# Variable_Voltage.net
KiCad netlist of a schematic drawn in EAGLE
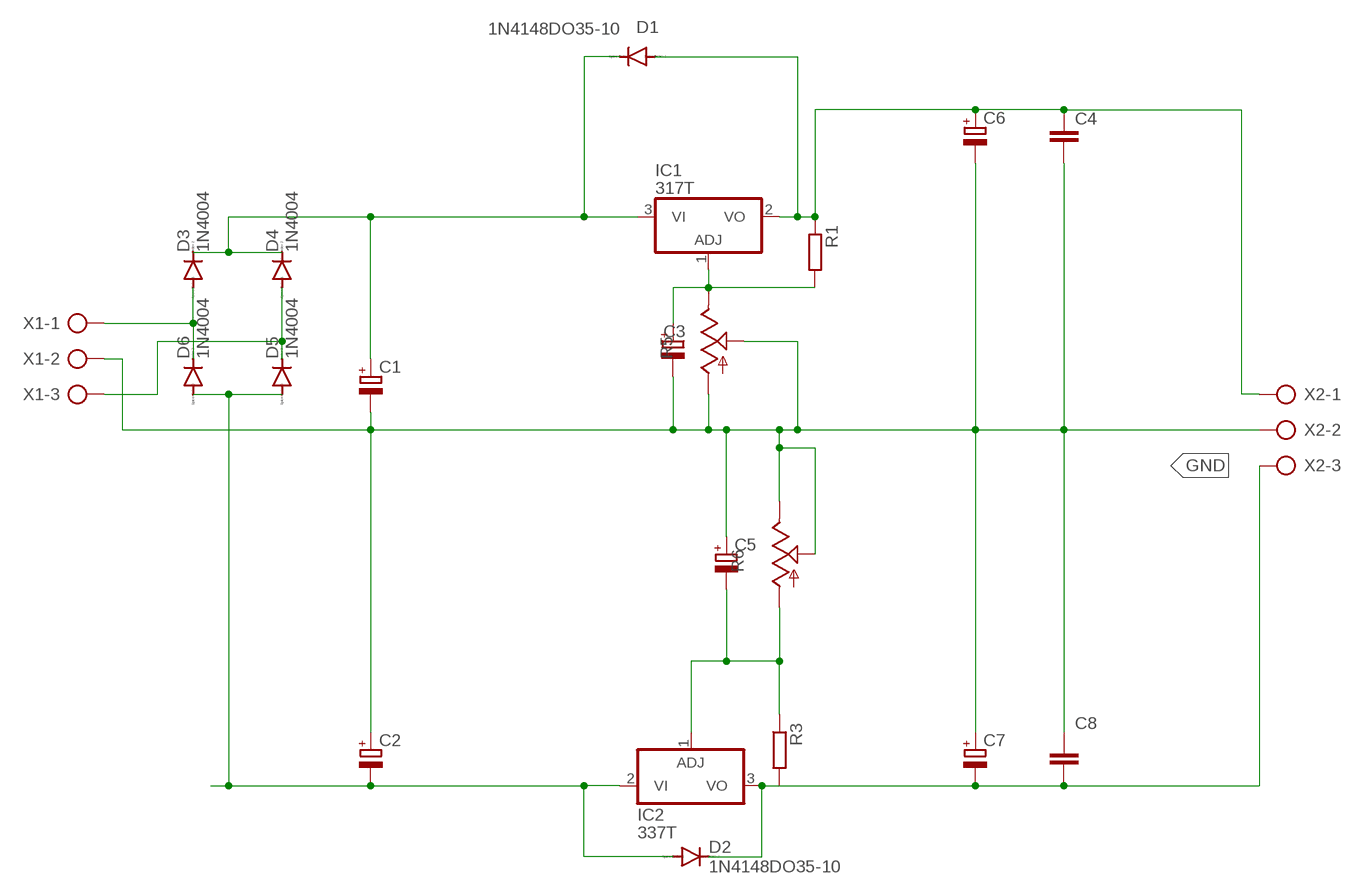
[diagram p0: schematic, sheet 1]

(export (version "E")
  (design (tool "Eeschema 10.0.6"))
  (components
    (comp (ref "C1")
      (value "CPOL-EUE5-8.5")
      (footprint "eagle-import:E5-8,5")
      (libsource (lib "eagle-import") (part "CPOL-EUE5-8.5"))
    )
    (comp (ref "C2")
      (value "CPOL-EUE5-8.5")
      (footprint "eagle-import:E5-8,5")
      (libsource (lib "eagle-import") (part "CPOL-EUE5-8.5"))
    )
    (comp (ref "C3")
      (value "CPOL-EUE2-4")
      (footprint "eagle-import:E2-4")
      (libsource (lib "eagle-import") (part "CPOL-EUE2-4"))
    )
    (comp (ref "C4")
      (value "C2,5-3")
      (footprint "eagle-import:C2.5-3")
      (libsource (lib "eagle-import") (part "C2,5-3"))
    )
    (comp (ref "C5")
      (value "CPOL-EUE2-4")
      (footprint "eagle-import:E2-4")
      (libsource (lib "eagle-import") (part "CPOL-EUE2-4"))
    )
    (comp (ref "C6")
      (value "CPOL-EUE2.5-4V")
      (footprint "eagle-import:E2,5RE")
      (libsource (lib "eagle-import") (part "CPOL-EUE2.5-4V"))
    )
    (comp (ref "C7")
      (value "CPOL-EUE2.5-4V")
      (footprint "eagle-import:E2,5RE")
      (libsource (lib "eagle-import") (part "CPOL-EUE2.5-4V"))
    )
    (comp (ref "C8")
      (value "C2,5-3")
      (footprint "eagle-import:C2.5-3")
      (libsource (lib "eagle-import") (part "C2,5-3"))
    )
    (comp (ref "D1")
      (value "1N4148DO35-10")
      (footprint "eagle-import:DO35-10")
      (libsource (lib "eagle-import") (part "1N4148DO35-10"))
    )
    (comp (ref "D2")
      (value "1N4148DO35-10")
      (footprint "eagle-import:DO35-10")
      (libsource (lib "eagle-import") (part "1N4148DO35-10"))
    )
    (comp (ref "D3")
      (value "1N4004")
      (footprint "eagle-import:DO41-10")
      (libsource (lib "eagle-import") (part "1N4004"))
    )
    (comp (ref "D4")
      (value "1N4004")
      (footprint "eagle-import:DO41-10")
      (libsource (lib "eagle-import") (part "1N4004"))
    )
    (comp (ref "D5")
      (value "1N4004")
      (footprint "eagle-import:DO41-10")
      (libsource (lib "eagle-import") (part "1N4004"))
    )
    (comp (ref "D6")
      (value "1N4004")
      (footprint "eagle-import:DO41-10")
      (libsource (lib "eagle-import") (part "1N4004"))
    )
    (comp (ref "IC1")
      (value "317T")
      (footprint "eagle-import:TO220H")
      (libsource (lib "eagle-import") (part "317T"))
    )
    (comp (ref "IC2")
      (value "337T")
      (footprint "eagle-import:TO220H")
      (libsource (lib "eagle-import") (part "337T"))
    )
    (comp (ref "R1")
      (value "R-EU_0204/7")
      (footprint "eagle-import:0204_7")
      (libsource (lib "eagle-import") (part "R-EU_0204/7"))
    )
    (comp (ref "R3")
      (value "R-EU_0204/7")
      (footprint "eagle-import:0204_7")
      (libsource (lib "eagle-import") (part "R-EU_0204/7"))
    )
    (comp (ref "R5")
      (value "TRIM_US-B25V")
      (footprint "eagle-import:B25V")
      (libsource (lib "eagle-import") (part "TRIM_US-B25V"))
    )
    (comp (ref "R6")
      (value "TRIM_US-B25V")
      (footprint "eagle-import:B25V")
      (libsource (lib "eagle-import") (part "TRIM_US-B25V"))
    )
    (comp (ref "X1")
      (value "AK300/3")
      (footprint "eagle-import:AK300_3")
      (libsource (lib "eagle-import") (part "AK300/3"))
    )
    (comp (ref "X2")
      (value "AK300/3")
      (footprint "eagle-import:AK300_3")
      (libsource (lib "eagle-import") (part "AK300/3"))
    )
  )
  (nets
    (net (code "1") (name "GND") (class "Default")
      (node (ref "C1") (pin "-") (pinfunction "-_-") (pintype "passive"))
      (node (ref "C2") (pin "+") (pinfunction "+_+") (pintype "passive"))
      (node (ref "C3") (pin "-") (pinfunction "-_-") (pintype "passive"))
      (node (ref "C4") (pin "2") (pinfunction "2_2") (pintype "passive"))
      (node (ref "C5") (pin "+") (pinfunction "+_+") (pintype "passive"))
      (node (ref "C6") (pin "-") (pinfunction "-_-") (pintype "passive"))
      (node (ref "C7") (pin "+") (pinfunction "+_+") (pintype "passive"))
      (node (ref "C8") (pin "1") (pinfunction "1_1") (pintype "passive"))
      (node (ref "R5") (pin "A") (pinfunction "A_A") (pintype "passive"))
      (node (ref "R5") (pin "S") (pinfunction "S_S") (pintype "passive"))
      (node (ref "R6") (pin "E") (pinfunction "E_E") (pintype "passive"))
      (node (ref "R6") (pin "S") (pinfunction "S_S") (pintype "passive"))
      (node (ref "X1") (pin "2") (pinfunction "KL_2") (pintype "passive"))
      (node (ref "X2") (pin "2") (pinfunction "KL_2") (pintype "passive"))
    )
    (net (code "2") (name "Net-(IC1-ADJ)") (class "Default")
      (node (ref "C3") (pin "+") (pinfunction "+_+") (pintype "passive"))
      (node (ref "IC1") (pin "1") (pinfunction "ADJ_1") (pintype "input"))
      (node (ref "R1") (pin "2") (pinfunction "2_2") (pintype "passive"))
      (node (ref "R5") (pin "E") (pinfunction "E_E") (pintype "passive"))
    )
    (net (code "3") (name "Net-(IC1-VI)") (class "Default")
      (node (ref "C1") (pin "+") (pinfunction "+_+") (pintype "passive"))
      (node (ref "D1") (pin "C") (pinfunction "C_C") (pintype "passive"))
      (node (ref "D3") (pin "C") (pinfunction "C_C") (pintype "passive"))
      (node (ref "D4") (pin "C") (pinfunction "C_C") (pintype "passive"))
      (node (ref "IC1") (pin "3") (pinfunction "VI_3") (pintype "input"))
    )
    (net (code "4") (name "Net-(IC1-VO)") (class "Default")
      (node (ref "C4") (pin "1") (pinfunction "1_1") (pintype "passive"))
      (node (ref "C6") (pin "+") (pinfunction "+_+") (pintype "passive"))
      (node (ref "D1") (pin "A") (pinfunction "A_A") (pintype "passive"))
      (node (ref "IC1") (pin "2") (pinfunction "VO_2") (pintype "passive"))
      (node (ref "R1") (pin "1") (pinfunction "1_1") (pintype "passive"))
      (node (ref "X2") (pin "1") (pinfunction "KL_1") (pintype "passive"))
    )
    (net (code "5") (name "Net-(IC2-ADJ)") (class "Default")
      (node (ref "C5") (pin "-") (pinfunction "-_-") (pintype "passive"))
      (node (ref "IC2") (pin "1") (pinfunction "ADJ_1") (pintype "input"))
      (node (ref "R3") (pin "1") (pinfunction "1_1") (pintype "passive"))
      (node (ref "R6") (pin "A") (pinfunction "A_A") (pintype "passive"))
    )
    (net (code "6") (name "Net-(IC2-VI)") (class "Default")
      (node (ref "C2") (pin "-") (pinfunction "-_-") (pintype "passive"))
      (node (ref "D2") (pin "A") (pinfunction "A_A") (pintype "passive"))
      (node (ref "D5") (pin "A") (pinfunction "A_A") (pintype "passive"))
      (node (ref "D6") (pin "A") (pinfunction "A_A") (pintype "passive"))
      (node (ref "IC2") (pin "2") (pinfunction "VI_2") (pintype "input"))
    )
    (net (code "7") (name "Net-(IC2-VO)") (class "Default")
      (node (ref "C7") (pin "-") (pinfunction "-_-") (pintype "passive"))
      (node (ref "C8") (pin "2") (pinfunction "2_2") (pintype "passive"))
      (node (ref "D2") (pin "C") (pinfunction "C_C") (pintype "passive"))
      (node (ref "IC2") (pin "3") (pinfunction "VO_3") (pintype "passive"))
      (node (ref "R3") (pin "2") (pinfunction "2_2") (pintype "passive"))
      (node (ref "X2") (pin "3") (pinfunction "KL_3") (pintype "passive"))
    )
    (net (code "8") (name "Net-(X1A-KL)") (class "Default")
      (node (ref "D3") (pin "A") (pinfunction "A_A") (pintype "passive"))
      (node (ref "D6") (pin "C") (pinfunction "C_C") (pintype "passive"))
      (node (ref "X1") (pin "1") (pinfunction "KL_1") (pintype "passive"))
    )
    (net (code "9") (name "Net-(X1C-KL)") (class "Default")
      (node (ref "D4") (pin "A") (pinfunction "A_A") (pintype "passive"))
      (node (ref "D5") (pin "C") (pinfunction "C_C") (pintype "passive"))
      (node (ref "X1") (pin "3") (pinfunction "KL_3") (pintype "passive"))
    )
  )
)
